# design1.net
KiCad netlist of a schematic drawn in EAGLE
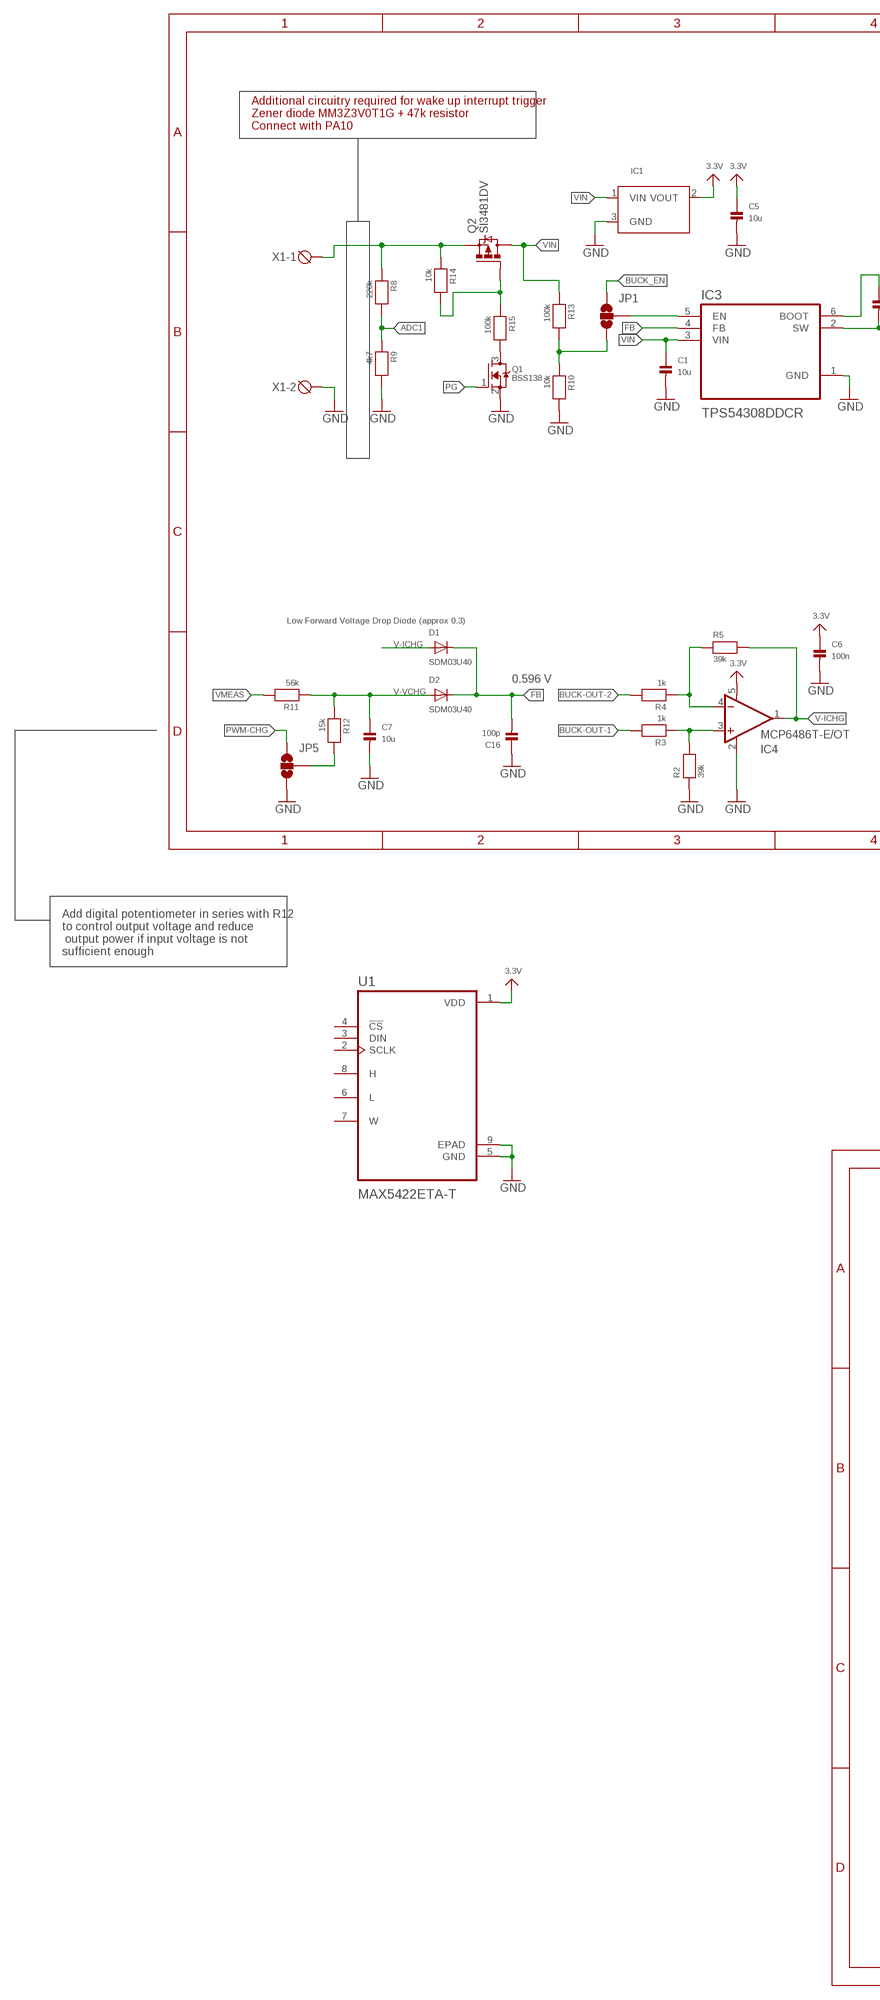
[diagram p0: schematic, sheet 1, part 1 of 2]
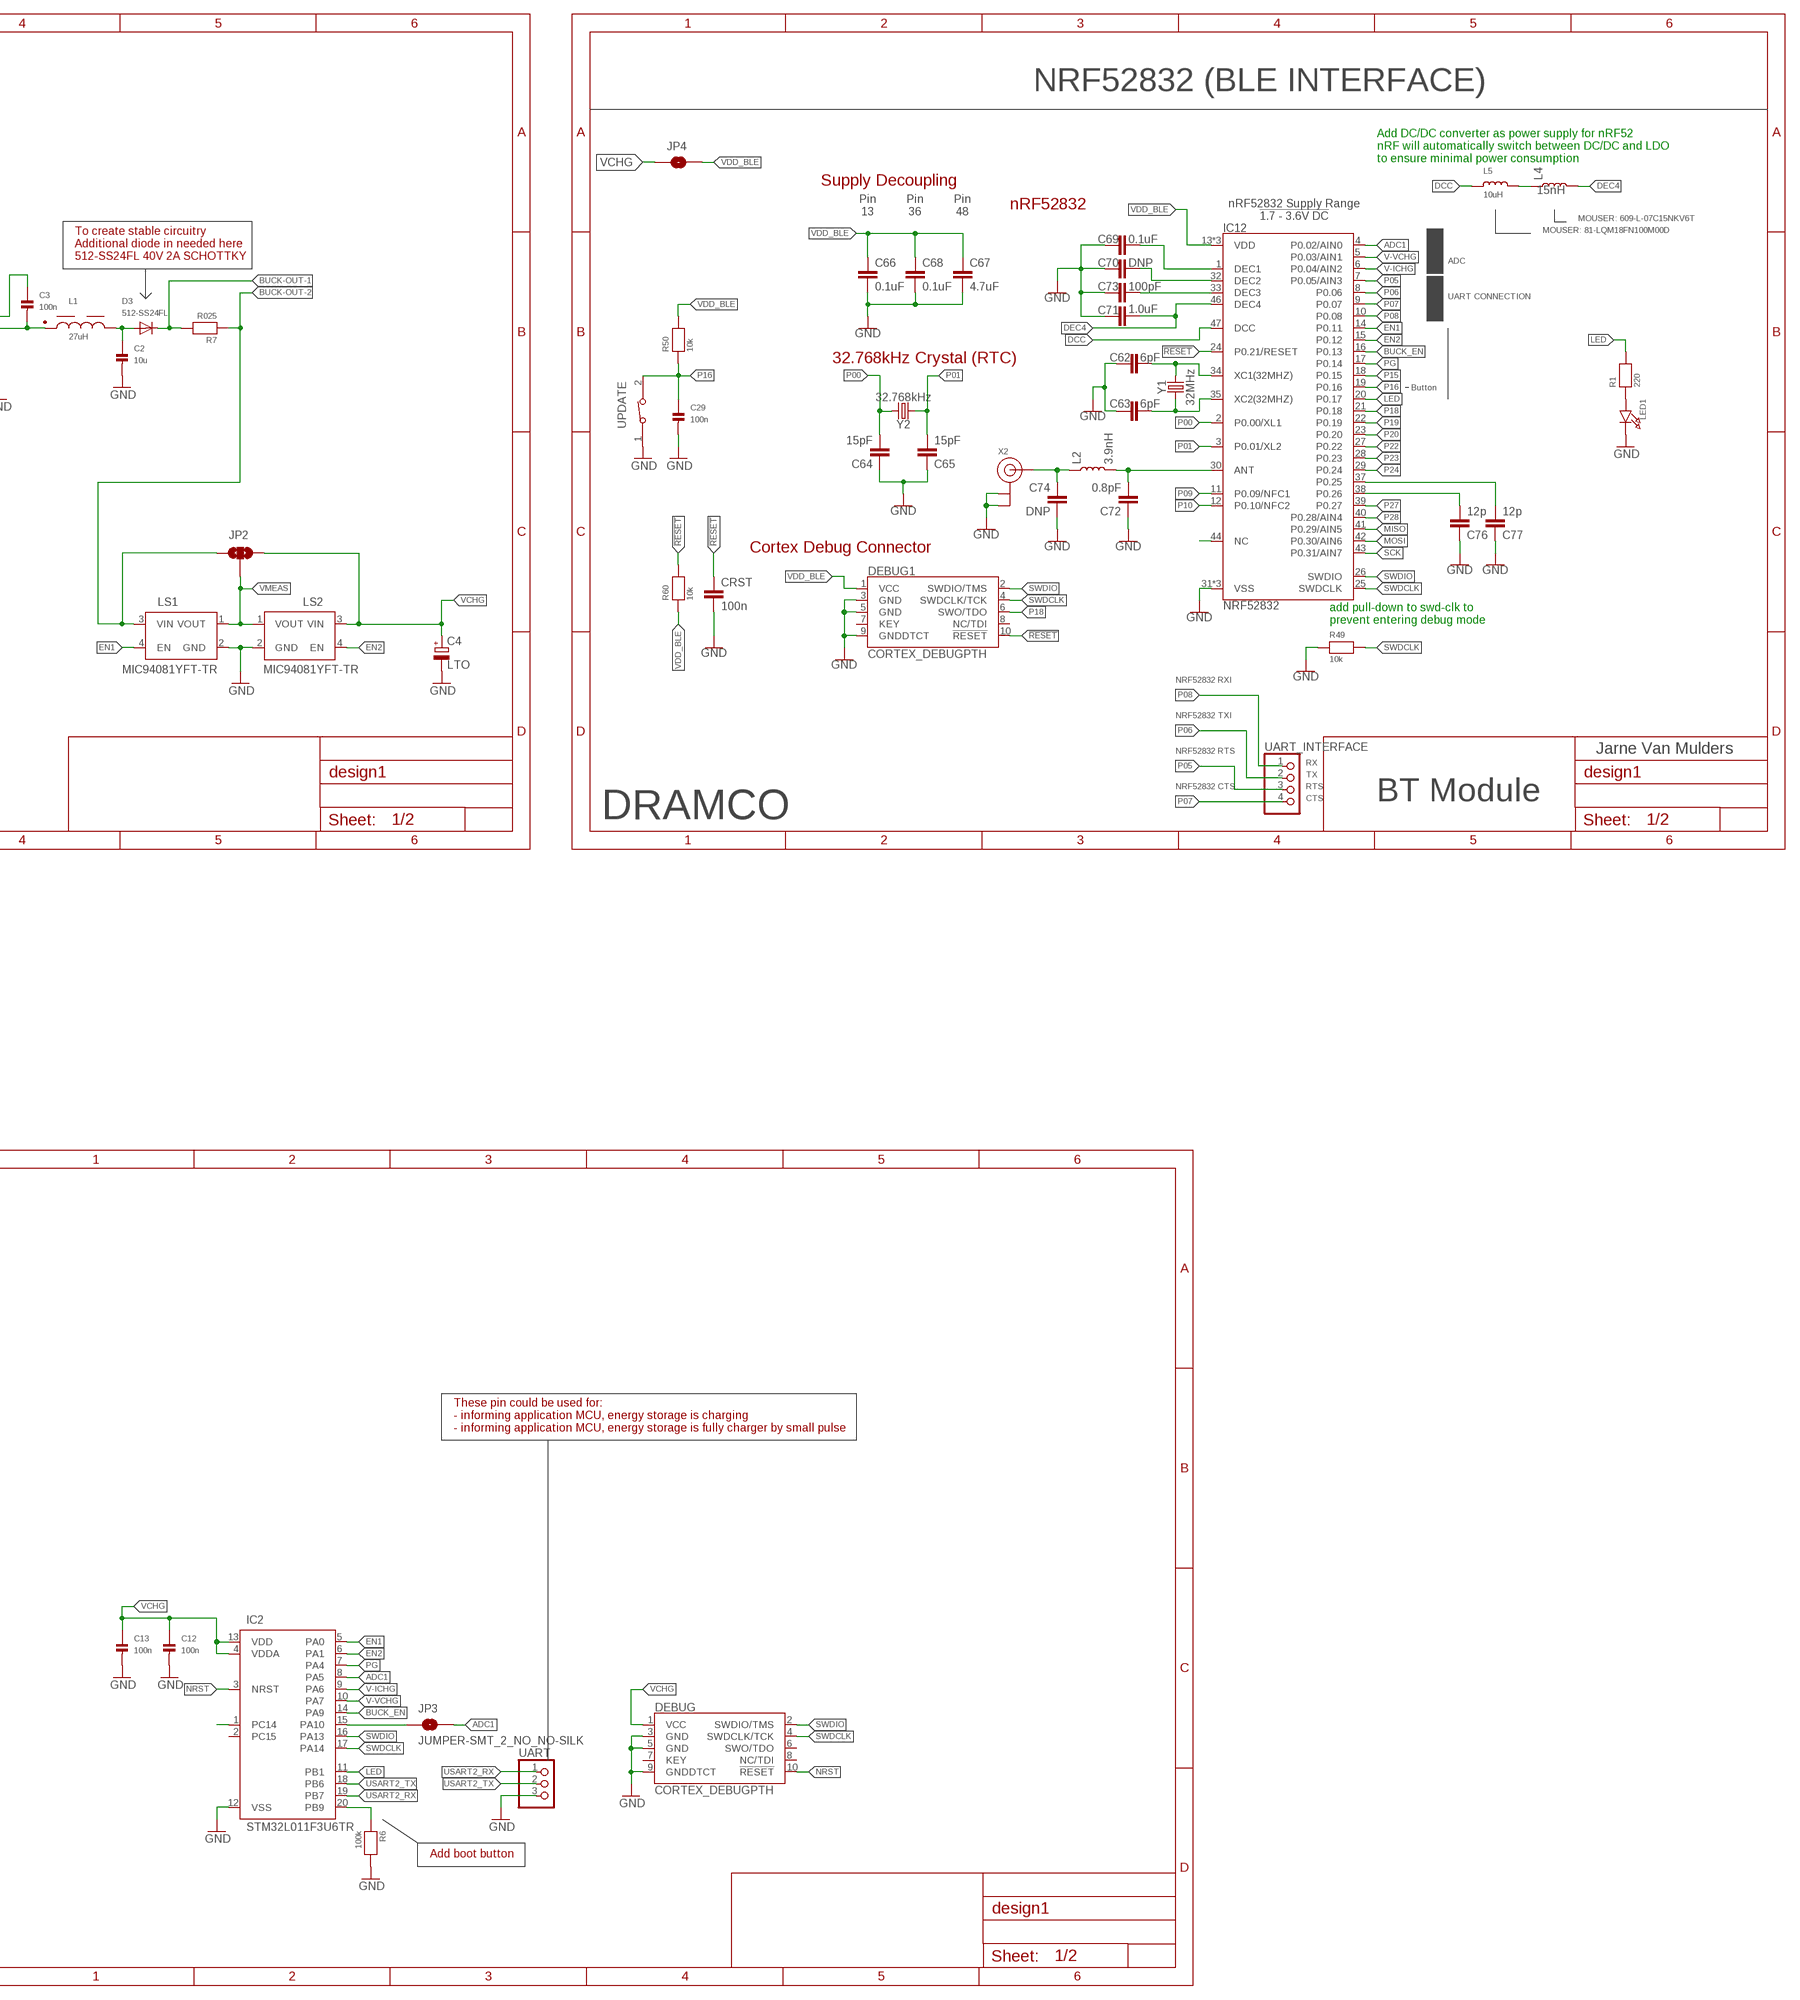
[diagram p1: schematic, sheet 1, part 2 of 2]

(export (version "E")
  (design (tool "Eeschema 10.0.6"))
  (components
    (comp (ref "C1")
      (value "10u")
      (footprint "eagle-import:0603")
      (libsource (lib "eagle-import") (part "CAP_CERAMIC0603"))
    )
    (comp (ref "C2")
      (value "10u")
      (footprint "eagle-import:0603")
      (libsource (lib "eagle-import") (part "CAP_CERAMIC0603"))
    )
    (comp (ref "C3")
      (value "100n")
      (footprint "eagle-import:0603")
      (libsource (lib "eagle-import") (part "CAP_CERAMIC0603"))
    )
    (comp (ref "C4")
      (value "LTO")
      (footprint "eagle-import:E5-10,5")
      (libsource (lib "eagle-import") (part "CPOL-EUE5-10.5"))
    )
    (comp (ref "C5")
      (value "10u")
      (footprint "eagle-import:0603")
      (libsource (lib "eagle-import") (part "CAP_CERAMIC0603"))
    )
    (comp (ref "C6")
      (value "100n")
      (footprint "eagle-import:0402")
      (libsource (lib "eagle-import") (part "CAP_CERAMIC0402"))
    )
    (comp (ref "C7")
      (value "10u")
      (footprint "eagle-import:0603")
      (libsource (lib "eagle-import") (part "CAP_CERAMIC0603"))
    )
    (comp (ref "C12")
      (value "100n")
      (footprint "eagle-import:0402")
      (libsource (lib "eagle-import") (part "CAP_CERAMIC0402"))
    )
    (comp (ref "C13")
      (value "100n")
      (footprint "eagle-import:0402")
      (libsource (lib "eagle-import") (part "CAP_CERAMIC0402"))
    )
    (comp (ref "C16")
      (value "100p")
      (footprint "eagle-import:0603")
      (libsource (lib "eagle-import") (part "CAP_CERAMIC0603"))
    )
    (comp (ref "C29")
      (value "100n")
      (footprint "eagle-import:0603")
      (libsource (lib "eagle-import") (part "CAP_CERAMIC0603"))
    )
    (comp (ref "C62")
      (value "6pF")
      (footprint "eagle-import:0402")
      (libsource (lib "eagle-import") (part "6PF-0402-50V-0.5%"))
    )
    (comp (ref "C63")
      (value "6pF")
      (footprint "eagle-import:0402")
      (libsource (lib "eagle-import") (part "6PF-0402-50V-0.5%"))
    )
    (comp (ref "C64")
      (value "15pF")
      (footprint "eagle-import:0402")
      (libsource (lib "eagle-import") (part "15PF-0402-50V-5%"))
    )
    (comp (ref "C65")
      (value "15pF")
      (footprint "eagle-import:0402")
      (libsource (lib "eagle-import") (part "15PF-0402-50V-5%"))
    )
    (comp (ref "C66")
      (value "0.1uF")
      (footprint "eagle-import:0402")
      (libsource (lib "eagle-import") (part "0.1UF-0402-16V-10%"))
    )
    (comp (ref "C67")
      (value "4.7uF")
      (footprint "eagle-import:0603")
      (libsource (lib "eagle-import") (part "4.7UF0603"))
    )
    (comp (ref "C68")
      (value "0.1uF")
      (footprint "eagle-import:0402")
      (libsource (lib "eagle-import") (part "0.1UF-0402-16V-10%"))
    )
    (comp (ref "C69")
      (value "0.1uF")
      (footprint "eagle-import:0402")
      (libsource (lib "eagle-import") (part "0.1UF-0402-16V-10%"))
    )
    (comp (ref "C70")
      (value "DNP")
      (footprint "eagle-import:0402")
      (libsource (lib "eagle-import") (part "CAP0402"))
    )
    (comp (ref "C71")
      (value "1.0uF")
      (footprint "eagle-import:0402")
      (libsource (lib "eagle-import") (part "1.0UF-0402-16V-10%"))
    )
    (comp (ref "C72")
      (value "0.8pF")
      (footprint "eagle-import:0402")
      (libsource (lib "eagle-import") (part "0.8PF-0402-50V-0.1PF"))
    )
    (comp (ref "C73")
      (value "100pF")
      (footprint "eagle-import:0402")
      (libsource (lib "eagle-import") (part "100PF-0402-50V-5%"))
    )
    (comp (ref "C74")
      (value "DNP")
      (footprint "eagle-import:0402")
      (libsource (lib "eagle-import") (part "CAP0402"))
    )
    (comp (ref "C76")
      (value "12p")
      (footprint "eagle-import:0402")
      (libsource (lib "eagle-import") (part "15PF-0402-50V-5%"))
    )
    (comp (ref "C77")
      (value "12p")
      (footprint "eagle-import:0402")
      (libsource (lib "eagle-import") (part "15PF-0402-50V-5%"))
    )
    (comp (ref "CRST")
      (value "100n")
      (footprint "eagle-import:C0603")
      (libsource (lib "eagle-import") (part "C-EUC0603"))
    )
    (comp (ref "D1")
      (value "SDM03U40")
      (footprint "eagle-import:SOD-523")
      (libsource (lib "eagle-import") (part "DIODESOD-523"))
    )
    (comp (ref "D2")
      (value "SDM03U40")
      (footprint "eagle-import:SOD-523")
      (libsource (lib "eagle-import") (part "DIODESOD-523"))
    )
    (comp (ref "D3")
      (value "512-SS24FL")
      (footprint "eagle-import:SOD-123")
      (libsource (lib "eagle-import") (part "DIODESOD-123"))
    )
    (comp (ref "DEBUG")
      (value "CORTEX_DEBUGPTH")
      (footprint "eagle-import:2X5-PTH-1.27MM")
      (libsource (lib "eagle-import") (part "CORTEX_DEBUGPTH"))
    )
    (comp (ref "DEBUG1")
      (value "CORTEX_DEBUGPTH")
      (footprint "eagle-import:2X5-PTH-1.27MM")
      (libsource (lib "eagle-import") (part "CORTEX_DEBUGPTH"))
    )
    (comp (ref "IC1")
      (value "VREG_SOT23")
      (footprint "eagle-import:SOT23-R")
      (libsource (lib "eagle-import") (part "VREG_SOT23"))
    )
    (comp (ref "IC2")
      (value "STM32L011F3U6TR")
      (footprint "eagle-import:QFN50P300X300X60-21N")
      (fields (field (name "MANUFACTURER") "STMicroelectronics"))
      (libsource (lib "eagle-import") (part "STM32L011F3U6TR"))
    )
    (comp (ref "IC3")
      (value "TPS54308DDCR")
      (footprint "eagle-import:SOT95P280X110-6N")
      (fields (field (name "MF") "Texas Instruments"))
      (libsource (lib "eagle-import") (part "TPS54308DDCR"))
    )
    (comp (ref "IC4")
      (value "MCP6486T-E/OT")
      (footprint "eagle-import:SOT23-5")
      (libsource (lib "eagle-import") (part "MCP6291T-E/OT"))
    )
    (comp (ref "IC12")
      (value "NRF52832")
      (footprint "eagle-import:QFN48-6X6MM")
      (libsource (lib "eagle-import") (part "NRF52832"))
    )
    (comp (ref "JP1")
      (value "JUMPER-SMT_3_NO_NO-SILK")
      (footprint "eagle-import:SMT-JUMPER_3_NO_NO-SILK")
      (libsource (lib "eagle-import") (part "JUMPER-SMT_3_NO_NO-SILK"))
    )
    (comp (ref "JP2")
      (value "JUMPER-SMT_3_NO_NO-SILK")
      (footprint "eagle-import:SMT-JUMPER_3_NO_NO-SILK")
      (libsource (lib "eagle-import") (part "JUMPER-SMT_3_NO_NO-SILK"))
    )
    (comp (ref "JP3")
      (value "JUMPER-SMT_2_NO_NO-SILK")
      (footprint "eagle-import:SMT-JUMPER_2_NO_NO-SILK")
      (libsource (lib "eagle-import") (part "JUMPER-SMT_2_NO_NO-SILK"))
    )
    (comp (ref "JP4")
      (value "JUMPER-SMT_2_NO_NO-SILK")
      (footprint "eagle-import:SMT-JUMPER_2_NO_NO-SILK")
      (libsource (lib "eagle-import") (part "JUMPER-SMT_2_NO_NO-SILK"))
    )
    (comp (ref "JP5")
      (value "JUMPER-SMT_3_NO_NO-SILK")
      (footprint "eagle-import:SMT-JUMPER_3_NO_NO-SILK")
      (libsource (lib "eagle-import") (part "JUMPER-SMT_3_NO_NO-SILK"))
    )
    (comp (ref "L1")
      (value "27uH")
      (footprint "eagle-import:WE-PD_7332_7345_PLASTIC_BASE")
      (libsource (lib "eagle-import") (part "WE-PD_7332_PLASTIC_7447789127"))
    )
    (comp (ref "L2")
      (value "3.9nH")
      (footprint "eagle-import:0402")
      (libsource (lib "eagle-import") (part "INDUCTOR-0402-3.9NH"))
    )
    (comp (ref "L4")
      (value "15nH")
      (footprint "eagle-import:0402")
      (libsource (lib "eagle-import") (part "INDUCTOR-0402-3.9NH"))
    )
    (comp (ref "L5")
      (value "10uH")
      (footprint "eagle-import:_0603MP")
      (libsource (lib "eagle-import") (part "INDUCTOR_0603MP"))
    )
    (comp (ref "LED1")
      (value "LED0805")
      (footprint "eagle-import:CHIPLED_0805")
      (libsource (lib "eagle-import") (part "LED0805"))
    )
    (comp (ref "LS1")
      (value "MIC94081YFT-TR")
      (footprint "eagle-import:IC_MIC94081YFT-TR")
      (fields (field (name "MF") "Microchip"))
      (libsource (lib "eagle-import") (part "MIC94081YFT-TR"))
    )
    (comp (ref "LS2")
      (value "MIC94081YFT-TR")
      (footprint "eagle-import:IC_MIC94081YFT-TR")
      (fields (field (name "MF") "Microchip"))
      (libsource (lib "eagle-import") (part "MIC94081YFT-TR"))
    )
    (comp (ref "Q1")
      (value "BSS138")
      (footprint "eagle-import:SOT23-R")
      (libsource (lib "eagle-import") (part "MOSFET-NREFLOW"))
    )
    (comp (ref "Q2")
      (value "SI3481DV")
      (footprint "eagle-import:TSOP-6.PAC")
      (libsource (lib "eagle-import") (part "SI3481DV"))
    )
    (comp (ref "R1")
      (value "220")
      (footprint "eagle-import:0603")
      (libsource (lib "eagle-import") (part "RESISTOR0603"))
    )
    (comp (ref "R2")
      (value "39k")
      (footprint "eagle-import:0603")
      (libsource (lib "eagle-import") (part "RESISTOR0603"))
    )
    (comp (ref "R3")
      (value "1k")
      (footprint "eagle-import:0603")
      (libsource (lib "eagle-import") (part "RESISTOR0603"))
    )
    (comp (ref "R4")
      (value "1k")
      (footprint "eagle-import:0603")
      (libsource (lib "eagle-import") (part "RESISTOR0603"))
    )
    (comp (ref "R5")
      (value "39k")
      (footprint "eagle-import:0603")
      (libsource (lib "eagle-import") (part "RESISTOR0603"))
    )
    (comp (ref "R6")
      (value "100k")
      (footprint "eagle-import:0603")
      (libsource (lib "eagle-import") (part "RESISTOR0603"))
    )
    (comp (ref "R7")
      (value "R025")
      (footprint "eagle-import:0603")
      (libsource (lib "eagle-import") (part "RESISTOR0603"))
    )
    (comp (ref "R8")
      (value "220k")
      (footprint "eagle-import:0603")
      (libsource (lib "eagle-import") (part "RESISTOR0603"))
    )
    (comp (ref "R9")
      (value "4k7")
      (footprint "eagle-import:0603")
      (libsource (lib "eagle-import") (part "RESISTOR0603"))
    )
    (comp (ref "R10")
      (value "10k")
      (footprint "eagle-import:0603")
      (libsource (lib "eagle-import") (part "RESISTOR0603"))
    )
    (comp (ref "R11")
      (value "56k")
      (footprint "eagle-import:0603")
      (libsource (lib "eagle-import") (part "RESISTOR0603"))
    )
    (comp (ref "R12")
      (value "15k")
      (footprint "eagle-import:0603")
      (libsource (lib "eagle-import") (part "RESISTOR0603"))
    )
    (comp (ref "R13")
      (value "100k")
      (footprint "eagle-import:0603")
      (libsource (lib "eagle-import") (part "RESISTOR0603"))
    )
    (comp (ref "R14")
      (value "10k")
      (footprint "eagle-import:0603")
      (libsource (lib "eagle-import") (part "RESISTOR0603"))
    )
    (comp (ref "R15")
      (value "100k")
      (footprint "eagle-import:0603")
      (libsource (lib "eagle-import") (part "RESISTOR0603"))
    )
    (comp (ref "R49")
      (value "10k")
      (footprint "eagle-import:0603")
      (libsource (lib "eagle-import") (part "RESISTOR0603"))
    )
    (comp (ref "R50")
      (value "10k")
      (footprint "eagle-import:0603")
      (libsource (lib "eagle-import") (part "RESISTOR0603"))
    )
    (comp (ref "R60")
      (value "10k")
      (footprint "eagle-import:0603")
      (libsource (lib "eagle-import") (part "RESISTOR0603"))
    )
    (comp (ref "U1")
      (value "MAX5422ETA-T")
      (footprint "eagle-import:SON65P300X300X80-9N")
      (fields (field (name "MF") "Analog Devices") (field (name "MP") "MAX5422ETA"))
      (libsource (lib "eagle-import") (part "MAX5422ETA-T"))
    )
    (comp (ref "UART")
      (value "HEADER-1X3ROUND")
      (footprint "eagle-import:1X03_ROUND")
      (libsource (lib "eagle-import") (part "HEADER-1X3ROUND"))
    )
    (comp (ref "UART_INTERFACE")
      (value "HEADER-1X4ROUND")
      (footprint "eagle-import:1X04_ROUND")
      (libsource (lib "eagle-import") (part "HEADER-1X4ROUND"))
    )
    (comp (ref "UPDATE")
      (value "434111043826")
      (footprint "eagle-import:434111043826")
      (libsource (lib "eagle-import") (part "434111043826"))
    )
    (comp (ref "X1")
      (value "DG3XX-02-5.0")
      (footprint "eagle-import:DG306-5.0-02P")
      (libsource (lib "eagle-import") (part "DG3XX-02-5.0"))
    )
    (comp (ref "X2")
      (value "ANTENNA_U.FL")
      (footprint "eagle-import:U.FL")
      (libsource (lib "eagle-import") (part "ANTENNA_U.FL"))
    )
    (comp (ref "Y1")
      (value "32MHz")
      (footprint "eagle-import:CRYSTAL-SMD-2.0X1.6MM")
      (libsource (lib "eagle-import") (part "CRYSTAL-32MHZ-SMD-2.0X1.6MM"))
    )
    (comp (ref "Y2")
      (value "32.768kHz")
      (footprint "eagle-import:CRYSTAL-SMD-3.2X1.5MM")
      (libsource (lib "eagle-import") (part "CRYSTAL-32.768KHZSMD-3.2X1.5"))
    )
  )
  (nets
    (net (code "1") (name "3.3V") (class "Default")
      (node (ref "C5") (pin "1") (pinfunction "P$1_1") (pintype "passive"))
      (node (ref "C6") (pin "1") (pinfunction "P$1_1") (pintype "passive"))
      (node (ref "IC1") (pin "2") (pinfunction "VOUT_2") (pintype "power_in"))
      (node (ref "IC4") (pin "5") (pinfunction "V+_5") (pintype "power_in"))
      (node (ref "U1") (pin "1") (pinfunction "VDD_1") (pintype "power_in"))
    )
    (net (code "2") (name "ADC1") (class "Default")
      (node (ref "IC12") (pin "4") (pinfunction "P0.02/AIN0_4") (pintype "bidirectional"))
      (node (ref "IC2") (pin "8") (pinfunction "PA5_8") (pintype "bidirectional"))
      (node (ref "JP3") (pin "2") (pinfunction "2_2") (pintype "passive"))
      (node (ref "R8") (pin "2") (pinfunction "2_2") (pintype "passive"))
      (node (ref "R9") (pin "1") (pinfunction "1_1") (pintype "passive"))
    )
    (net (code "3") (name "BUCK-OUT-1") (class "Default")
      (node (ref "D3") (pin "C") (pinfunction "C_C") (pintype "passive"))
      (node (ref "R3") (pin "2") (pinfunction "2_2") (pintype "passive"))
      (node (ref "R7") (pin "2") (pinfunction "2_2") (pintype "passive"))
    )
    (net (code "4") (name "BUCK-OUT-2") (class "Default")
      (node (ref "JP2") (pin "1") (pinfunction "1_1") (pintype "passive"))
      (node (ref "LS1") (pin "3") (pinfunction "VIN_3") (pintype "input"))
      (node (ref "R4") (pin "2") (pinfunction "2_2") (pintype "passive"))
      (node (ref "R7") (pin "1") (pinfunction "1_1") (pintype "passive"))
    )
    (net (code "5") (name "BUCK_EN") (class "Default")
      (node (ref "IC12") (pin "16") (pinfunction "P0.13_16") (pintype "bidirectional"))
      (node (ref "IC2") (pin "14") (pinfunction "PA9_14") (pintype "bidirectional"))
      (node (ref "JP1") (pin "3") (pinfunction "3_3") (pintype "passive"))
    )
    (net (code "6") (name "DCC") (class "Default")
      (node (ref "IC12") (pin "47") (pinfunction "DCC_47") (pintype "bidirectional"))
      (node (ref "L5") (pin "1") (pinfunction "1_1") (pintype "passive"))
    )
    (net (code "7") (name "DEC4") (class "Default")
      (node (ref "C71") (pin "2") (pinfunction "2_2") (pintype "passive"))
      (node (ref "IC12") (pin "46") (pinfunction "DEC4_46") (pintype "bidirectional"))
      (node (ref "L4") (pin "2") (pinfunction "2_2") (pintype "passive"))
    )
    (net (code "8") (name "EN1") (class "Default")
      (node (ref "IC12") (pin "14") (pinfunction "P0.11_14") (pintype "bidirectional"))
      (node (ref "IC2") (pin "5") (pinfunction "PA0_5") (pintype "bidirectional"))
      (node (ref "LS1") (pin "4") (pinfunction "EN_4") (pintype "input"))
    )
    (net (code "9") (name "EN2") (class "Default")
      (node (ref "IC12") (pin "15") (pinfunction "P0.12_15") (pintype "bidirectional"))
      (node (ref "IC2") (pin "6") (pinfunction "PA1_6") (pintype "bidirectional"))
      (node (ref "LS2") (pin "4") (pinfunction "EN_4") (pintype "input"))
    )
    (net (code "10") (name "FB") (class "Default")
      (node (ref "C16") (pin "2") (pinfunction "P$2_2") (pintype "passive"))
      (node (ref "D1") (pin "K") (pinfunction "C_K") (pintype "passive"))
      (node (ref "D2") (pin "K") (pinfunction "C_K") (pintype "passive"))
      (node (ref "IC3") (pin "4") (pinfunction "FB_4") (pintype "input"))
    )
    (net (code "11") (name "GND") (class "Default")
      (node (ref "C1") (pin "2") (pinfunction "P$2_2") (pintype "passive"))
      (node (ref "C12") (pin "2") (pinfunction "P$2_2") (pintype "passive"))
      (node (ref "C13") (pin "2") (pinfunction "P$2_2") (pintype "passive"))
      (node (ref "C16") (pin "1") (pinfunction "P$1_1") (pintype "passive"))
      (node (ref "C2") (pin "2") (pinfunction "P$2_2") (pintype "passive"))
      (node (ref "C29") (pin "2") (pinfunction "P$2_2") (pintype "passive"))
      (node (ref "C4") (pin "-") (pinfunction "-_-") (pintype "passive"))
      (node (ref "C5") (pin "2") (pinfunction "P$2_2") (pintype "passive"))
      (node (ref "C6") (pin "2") (pinfunction "P$2_2") (pintype "passive"))
      (node (ref "C62") (pin "1") (pinfunction "1_1") (pintype "passive"))
      (node (ref "C63") (pin "2") (pinfunction "2_2") (pintype "passive"))
      (node (ref "C64") (pin "1") (pinfunction "1_1") (pintype "passive"))
      (node (ref "C65") (pin "1") (pinfunction "1_1") (pintype "passive"))
      (node (ref "C66") (pin "2") (pinfunction "2_2") (pintype "passive"))
      (node (ref "C67") (pin "2") (pinfunction "2_2") (pintype "passive"))
      (node (ref "C68") (pin "2") (pinfunction "2_2") (pintype "passive"))
      (node (ref "C69") (pin "1") (pinfunction "1_1") (pintype "passive"))
      (node (ref "C7") (pin "2") (pinfunction "P$2_2") (pintype "passive"))
      (node (ref "C70") (pin "1") (pinfunction "1_1") (pintype "passive"))
      (node (ref "C71") (pin "1") (pinfunction "1_1") (pintype "passive"))
      (node (ref "C72") (pin "1") (pinfunction "1_1") (pintype "passive"))
      (node (ref "C73") (pin "1") (pinfunction "1_1") (pintype "passive"))
      (node (ref "C74") (pin "2") (pinfunction "2_2") (pintype "passive"))
      (node (ref "C76") (pin "1") (pinfunction "1_1") (pintype "passive"))
      (node (ref "C77") (pin "1") (pinfunction "1_1") (pintype "passive"))
      (node (ref "CRST") (pin "2") (pinfunction "2_2") (pintype "passive"))
      (node (ref "DEBUG") (pin "3") (pinfunction "GND_3") (pintype "bidirectional"))
      (node (ref "DEBUG") (pin "5") (pinfunction "GND_5") (pintype "bidirectional"))
      (node (ref "DEBUG") (pin "9") (pinfunction "GNDDTCT_9") (pintype "bidirectional"))
      (node (ref "DEBUG1") (pin "3") (pinfunction "GND_3") (pintype "bidirectional"))
      (node (ref "DEBUG1") (pin "5") (pinfunction "GND_5") (pintype "bidirectional"))
      (node (ref "DEBUG1") (pin "9") (pinfunction "GNDDTCT_9") (pintype "bidirectional"))
      (node (ref "IC1") (pin "3") (pinfunction "GND_3") (pintype "power_in"))
      (node (ref "IC12") (pin "31") (pinfunction "VSS_31") (pintype "bidirectional"))
      (node (ref "IC12") (pin "45") (pinfunction "VSS_45") (pintype "bidirectional"))
      (node (ref "IC12") (pin "EP") (pinfunction "VSS_EP") (pintype "bidirectional"))
      (node (ref "IC2") (pin "12") (pinfunction "VSS_12") (pintype "bidirectional"))
      (node (ref "IC3") (pin "1") (pinfunction "GND_1") (pintype "power_in"))
      (node (ref "IC4") (pin "2") (pinfunction "V-_2") (pintype "power_in"))
      (node (ref "JP5") (pin "1") (pinfunction "1_1") (pintype "passive"))
      (node (ref "LED1") (pin "C") (pinfunction "C_C") (pintype "passive"))
      (node (ref "LS1") (pin "2") (pinfunction "GND_2") (pintype "power_in"))
      (node (ref "LS2") (pin "2") (pinfunction "GND_2") (pintype "power_in"))
      (node (ref "Q1") (pin "2") (pinfunction "S_2") (pintype "bidirectional"))
      (node (ref "R10") (pin "2") (pinfunction "2_2") (pintype "passive"))
      (node (ref "R2") (pin "1") (pinfunction "1_1") (pintype "passive"))
      (node (ref "R49") (pin "1") (pinfunction "1_1") (pintype "passive"))
      (node (ref "R6") (pin "2") (pinfunction "2_2") (pintype "passive"))
      (node (ref "R9") (pin "2") (pinfunction "2_2") (pintype "passive"))
      (node (ref "U1") (pin "5") (pinfunction "GND_5") (pintype "power_in"))
      (node (ref "U1") (pin "9") (pinfunction "EPAD_9") (pintype "power_in"))
      (node (ref "UART") (pin "3") (pinfunction "3_3") (pintype "passive"))
      (node (ref "UPDATE") (pin "1") (pinfunction "1_1") (pintype "passive"))
      (node (ref "X1") (pin "2") (pinfunction "KL_2") (pintype "passive"))
      (node (ref "X2") (pin "1") (pinfunction "GND_1") (pintype "passive"))
      (node (ref "X2") (pin "2") (pinfunction "GND_2") (pintype "passive"))
    )
    (net (code "12") (name "LED") (class "Default")
      (node (ref "IC12") (pin "20") (pinfunction "P0.17_20") (pintype "bidirectional"))
      (node (ref "IC2") (pin "11") (pinfunction "PB1_11") (pintype "bidirectional"))
      (node (ref "R1") (pin "2") (pinfunction "2_2") (pintype "passive"))
    )
    (net (code "13") (name "MISO") (class "Default")
      (node (ref "IC12") (pin "41") (pinfunction "P0.29/AIN5_41") (pintype "bidirectional"))
    )
    (net (code "14") (name "MOSI") (class "Default")
      (node (ref "IC12") (pin "42") (pinfunction "P0.30/AIN6_42") (pintype "bidirectional"))
    )
    (net (code "15") (name "NRST") (class "Default")
      (node (ref "DEBUG") (pin "10") (pinfunction "~{RESET}_10") (pintype "bidirectional"))
      (node (ref "IC2") (pin "3") (pinfunction "NRST_3") (pintype "bidirectional"))
    )
    (net (code "16") (name "Net-(C2-P$1)") (class "Default")
      (node (ref "C2") (pin "1") (pinfunction "P$1_1") (pintype "passive"))
      (node (ref "D3") (pin "A") (pinfunction "A_A") (pintype "passive"))
      (node (ref "L1") (pin "2") (pinfunction "2_2") (pintype "passive"))
    )
    (net (code "17") (name "Net-(C3-P$1)") (class "Default")
      (node (ref "C3") (pin "1") (pinfunction "P$1_1") (pintype "passive"))
      (node (ref "IC3") (pin "6") (pinfunction "BOOT_6") (pintype "output"))
    )
    (net (code "18") (name "Net-(C3-P$2)") (class "Default")
      (node (ref "C3") (pin "2") (pinfunction "P$2_2") (pintype "passive"))
      (node (ref "IC3") (pin "2") (pinfunction "SW_2") (pintype "output"))
      (node (ref "L1") (pin "1") (pinfunction "1_1") (pintype "passive"))
    )
    (net (code "19") (name "Net-(IC2-PA10)") (class "Default")
      (node (ref "IC2") (pin "15") (pinfunction "PA10_15") (pintype "bidirectional"))
      (node (ref "JP3") (pin "1") (pinfunction "1_1") (pintype "passive"))
    )
    (net (code "20") (name "Net-(IC2-PB9)") (class "Default")
      (node (ref "IC2") (pin "20") (pinfunction "PB9_20") (pintype "bidirectional"))
      (node (ref "R6") (pin "1") (pinfunction "1_1") (pintype "passive"))
    )
    (net (code "21") (name "Net-(IC3-EN)") (class "Default")
      (node (ref "IC3") (pin "5") (pinfunction "EN_5") (pintype "input"))
      (node (ref "JP1") (pin "2") (pinfunction "2_2") (pintype "passive"))
    )
    (net (code "22") (name "Net-(IC4-+IN)") (class "Default")
      (node (ref "IC4") (pin "3") (pinfunction "+IN_3") (pintype "input"))
      (node (ref "R2") (pin "2") (pinfunction "2_2") (pintype "passive"))
      (node (ref "R3") (pin "1") (pinfunction "1_1") (pintype "passive"))
    )
    (net (code "23") (name "Net-(IC4--IN)") (class "Default")
      (node (ref "IC4") (pin "4") (pinfunction "-IN_4") (pintype "input"))
      (node (ref "R4") (pin "1") (pinfunction "1_1") (pintype "passive"))
      (node (ref "R5") (pin "1") (pinfunction "1_1") (pintype "passive"))
    )
    (net (code "24") (name "Net-(IC12-ANT)") (class "Default")
      (node (ref "C72") (pin "2") (pinfunction "2_2") (pintype "passive"))
      (node (ref "IC12") (pin "30") (pinfunction "ANT_30") (pintype "bidirectional"))
      (node (ref "L2") (pin "2") (pinfunction "2_2") (pintype "passive"))
    )
    (net (code "25") (name "Net-(IC12-DEC1)") (class "Default")
      (node (ref "C69") (pin "2") (pinfunction "2_2") (pintype "passive"))
      (node (ref "IC12") (pin "1") (pinfunction "DEC1_1") (pintype "bidirectional"))
    )
    (net (code "26") (name "Net-(IC12-DEC2)") (class "Default")
      (node (ref "C70") (pin "2") (pinfunction "2_2") (pintype "passive"))
      (node (ref "IC12") (pin "32") (pinfunction "DEC2_32") (pintype "bidirectional"))
    )
    (net (code "27") (name "Net-(IC12-DEC3)") (class "Default")
      (node (ref "C73") (pin "2") (pinfunction "2_2") (pintype "passive"))
      (node (ref "IC12") (pin "33") (pinfunction "DEC3_33") (pintype "bidirectional"))
    )
    (net (code "28") (name "Net-(IC12-P0.25)") (class "Default")
      (node (ref "C77") (pin "2") (pinfunction "2_2") (pintype "passive"))
      (node (ref "IC12") (pin "37") (pinfunction "P0.25_37") (pintype "bidirectional"))
    )
    (net (code "29") (name "Net-(IC12-P0.26)") (class "Default")
      (node (ref "C76") (pin "2") (pinfunction "2_2") (pintype "passive"))
      (node (ref "IC12") (pin "38") (pinfunction "P0.26_38") (pintype "bidirectional"))
    )
    (net (code "30") (name "Net-(IC12-XC1(32MHZ))") (class "Default")
      (node (ref "C62") (pin "2") (pinfunction "2_2") (pintype "passive"))
      (node (ref "IC12") (pin "34") (pinfunction "XC1(32MHZ)_34") (pintype "bidirectional"))
      (node (ref "Y1") (pin "3") (pinfunction "2_3") (pintype "passive"))
    )
    (net (code "31") (name "Net-(IC12-XC2(32MHZ))") (class "Default")
      (node (ref "C63") (pin "1") (pinfunction "1_1") (pintype "passive"))
      (node (ref "IC12") (pin "35") (pinfunction "XC2(32MHZ)_35") (pintype "bidirectional"))
      (node (ref "Y1") (pin "1") (pinfunction "1_1") (pintype "passive"))
    )
    (net (code "32") (name "Net-(JP1-Pad1)") (class "Default")
      (node (ref "JP1") (pin "1") (pinfunction "1_1") (pintype "passive"))
      (node (ref "R10") (pin "1") (pinfunction "1_1") (pintype "passive"))
      (node (ref "R13") (pin "2") (pinfunction "2_2") (pintype "passive"))
    )
    (net (code "33") (name "Net-(JP5-Pad2)") (class "Default")
      (node (ref "JP5") (pin "2") (pinfunction "2_2") (pintype "passive"))
      (node (ref "R12") (pin "2") (pinfunction "2_2") (pintype "passive"))
    )
    (net (code "34") (name "Net-(L4-Pad1)") (class "Default")
      (node (ref "L4") (pin "1") (pinfunction "1_1") (pintype "passive"))
      (node (ref "L5") (pin "2") (pinfunction "2_2") (pintype "passive"))
    )
    (net (code "35") (name "Net-(LED1-PadA)") (class "Default")
      (node (ref "LED1") (pin "A") (pinfunction "A_A") (pintype "passive"))
      (node (ref "R1") (pin "1") (pinfunction "1_1") (pintype "passive"))
    )
    (net (code "36") (name "Net-(Q1-D)") (class "Default")
      (node (ref "Q1") (pin "3") (pinfunction "D_3") (pintype "bidirectional"))
      (node (ref "R15") (pin "2") (pinfunction "2_2") (pintype "passive"))
    )
    (net (code "37") (name "Net-(Q2-G)") (class "Default")
      (node (ref "Q2") (pin "3") (pinfunction "G_3") (pintype "passive"))
      (node (ref "R14") (pin "2") (pinfunction "2_2") (pintype "passive"))
      (node (ref "R15") (pin "1") (pinfunction "1_1") (pintype "passive"))
    )
    (net (code "38") (name "Net-(Q2-S)") (class "Default")
      (node (ref "Q2") (pin "4") (pinfunction "S_4") (pintype "passive"))
      (node (ref "R14") (pin "1") (pinfunction "1_1") (pintype "passive"))
      (node (ref "R8") (pin "1") (pinfunction "1_1") (pintype "passive"))
      (node (ref "X1") (pin "1") (pinfunction "KL_1") (pintype "passive"))
    )
    (net (code "39") (name "Net-(X2-SIGNAL)") (class "Default")
      (node (ref "C74") (pin "1") (pinfunction "1_1") (pintype "passive"))
      (node (ref "L2") (pin "1") (pinfunction "1_1") (pintype "passive"))
      (node (ref "X2") (pin "3") (pinfunction "SIGNAL_3") (pintype "passive"))
    )
    (net (code "40") (name "P00") (class "Default")
      (node (ref "C64") (pin "2") (pinfunction "2_2") (pintype "passive"))
      (node (ref "IC12") (pin "2") (pinfunction "P0.00/XL1_2") (pintype "bidirectional"))
      (node (ref "Y2") (pin "P$2") (pinfunction "2_P$2") (pintype "passive"))
    )
    (net (code "41") (name "P01") (class "Default")
      (node (ref "C65") (pin "2") (pinfunction "2_2") (pintype "passive"))
      (node (ref "IC12") (pin "3") (pinfunction "P0.01/XL2_3") (pintype "bidirectional"))
      (node (ref "Y2") (pin "P$1") (pinfunction "1_P$1") (pintype "passive"))
    )
    (net (code "42") (name "P05") (class "Default")
      (node (ref "IC12") (pin "7") (pinfunction "P0.05/AIN3_7") (pintype "bidirectional"))
      (node (ref "UART_INTERFACE") (pin "3") (pinfunction "3_3") (pintype "passive"))
    )
    (net (code "43") (name "P06") (class "Default")
      (node (ref "IC12") (pin "8") (pinfunction "P0.06_8") (pintype "bidirectional"))
      (node (ref "UART_INTERFACE") (pin "2") (pinfunction "2_2") (pintype "passive"))
    )
    (net (code "44") (name "P07") (class "Default")
      (node (ref "IC12") (pin "9") (pinfunction "P0.07_9") (pintype "bidirectional"))
      (node (ref "UART_INTERFACE") (pin "4") (pinfunction "4_4") (pintype "passive"))
    )
    (net (code "45") (name "P08") (class "Default")
      (node (ref "IC12") (pin "10") (pinfunction "P0.08_10") (pintype "bidirectional"))
      (node (ref "UART_INTERFACE") (pin "1") (pinfunction "1_1") (pintype "passive"))
    )
    (net (code "46") (name "P09") (class "Default")
      (node (ref "IC12") (pin "11") (pinfunction "P0.09/NFC1_11") (pintype "bidirectional"))
    )
    (net (code "47") (name "P10") (class "Default")
      (node (ref "IC12") (pin "12") (pinfunction "P0.10/NFC2_12") (pintype "bidirectional"))
    )
    (net (code "48") (name "P15") (class "Default")
      (node (ref "IC12") (pin "18") (pinfunction "P0.15_18") (pintype "bidirectional"))
    )
    (net (code "49") (name "P16") (class "Default")
      (node (ref "C29") (pin "1") (pinfunction "P$1_1") (pintype "passive"))
      (node (ref "IC12") (pin "19") (pinfunction "P0.16_19") (pintype "bidirectional"))
      (node (ref "R50") (pin "1") (pinfunction "1_1") (pintype "passive"))
      (node (ref "UPDATE") (pin "2") (pinfunction "2_2") (pintype "passive"))
    )
    (net (code "50") (name "P18") (class "Default")
      (node (ref "DEBUG1") (pin "6") (pinfunction "SWO/TDO_6") (pintype "bidirectional"))
      (node (ref "IC12") (pin "21") (pinfunction "P0.18_21") (pintype "bidirectional"))
    )
    (net (code "51") (name "P19") (class "Default")
      (node (ref "IC12") (pin "22") (pinfunction "P0.19_22") (pintype "bidirectional"))
    )
    (net (code "52") (name "P20") (class "Default")
      (node (ref "IC12") (pin "23") (pinfunction "P0.20_23") (pintype "bidirectional"))
    )
    (net (code "53") (name "P22") (class "Default")
      (node (ref "IC12") (pin "27") (pinfunction "P0.22_27") (pintype "bidirectional"))
    )
    (net (code "54") (name "P23") (class "Default")
      (node (ref "IC12") (pin "28") (pinfunction "P0.23_28") (pintype "bidirectional"))
    )
    (net (code "55") (name "P24") (class "Default")
      (node (ref "IC12") (pin "29") (pinfunction "P0.24_29") (pintype "bidirectional"))
    )
    (net (code "56") (name "P27") (class "Default")
      (node (ref "IC12") (pin "39") (pinfunction "P0.27_39") (pintype "bidirectional"))
    )
    (net (code "57") (name "P28") (class "Default")
      (node (ref "IC12") (pin "40") (pinfunction "P0.28/AIN4_40") (pintype "bidirectional"))
    )
    (net (code "58") (name "PG") (class "Default")
      (node (ref "IC12") (pin "17") (pinfunction "P0.14_17") (pintype "bidirectional"))
      (node (ref "IC2") (pin "7") (pinfunction "PA4_7") (pintype "bidirectional"))
      (node (ref "Q1") (pin "1") (pinfunction "G_1") (pintype "bidirectional"))
    )
    (net (code "59") (name "PWM-CHG") (class "Default")
      (node (ref "JP5") (pin "3") (pinfunction "3_3") (pintype "passive"))
    )
    (net (code "60") (name "SCK") (class "Default")
      (node (ref "IC12") (pin "43") (pinfunction "P0.31/AIN7_43") (pintype "bidirectional"))
    )
    (net (code "61") (name "SWDCLK") (class "Default")
      (node (ref "DEBUG") (pin "4") (pinfunction "SWDCLK/TCK_4") (pintype "bidirectional"))
      (node (ref "DEBUG1") (pin "4") (pinfunction "SWDCLK/TCK_4") (pintype "bidirectional"))
      (node (ref "IC12") (pin "25") (pinfunction "SWDCLK_25") (pintype "bidirectional"))
      (node (ref "IC2") (pin "17") (pinfunction "PA14_17") (pintype "bidirectional"))
      (node (ref "R49") (pin "2") (pinfunction "2_2") (pintype "passive"))
    )
    (net (code "62") (name "SWDIO") (class "Default")
      (node (ref "DEBUG") (pin "2") (pinfunction "SWDIO/TMS_2") (pintype "bidirectional"))
      (node (ref "DEBUG1") (pin "2") (pinfunction "SWDIO/TMS_2") (pintype "bidirectional"))
      (node (ref "IC12") (pin "26") (pinfunction "SWDIO_26") (pintype "bidirectional"))
      (node (ref "IC2") (pin "16") (pinfunction "PA13_16") (pintype "bidirectional"))
    )
    (net (code "63") (name "USART2_RX") (class "Default")
      (node (ref "IC2") (pin "19") (pinfunction "PB7_19") (pintype "bidirectional"))
      (node (ref "UART") (pin "1") (pinfunction "1_1") (pintype "passive"))
    )
    (net (code "64") (name "USART2_TX") (class "Default")
      (node (ref "IC2") (pin "18") (pinfunction "PB6_18") (pintype "bidirectional"))
      (node (ref "UART") (pin "2") (pinfunction "2_2") (pintype "passive"))
    )
    (net (code "65") (name "V-ICHG") (class "Default")
      (node (ref "D1") (pin "A") (pinfunction "A_A") (pintype "passive"))
      (node (ref "IC12") (pin "6") (pinfunction "P0.04/AIN2_6") (pintype "bidirectional"))
      (node (ref "IC2") (pin "9") (pinfunction "PA6_9") (pintype "bidirectional"))
      (node (ref "IC4") (pin "1") (pinfunction "OUT_1") (pintype "output"))
      (node (ref "R5") (pin "2") (pinfunction "2_2") (pintype "passive"))
    )
    (net (code "66") (name "V-VCHG") (class "Default")
      (node (ref "C7") (pin "1") (pinfunction "P$1_1") (pintype "passive"))
      (node (ref "D2") (pin "A") (pinfunction "A_A") (pintype "passive"))
      (node (ref "IC12") (pin "5") (pinfunction "P0.03/AIN1_5") (pintype "bidirectional"))
      (node (ref "IC2") (pin "10") (pinfunction "PA7_10") (pintype "bidirectional"))
      (node (ref "R11") (pin "1") (pinfunction "1_1") (pintype "passive"))
      (node (ref "R12") (pin "1") (pinfunction "1_1") (pintype "passive"))
    )
    (net (code "67") (name "VCHG") (class "Default")
      (node (ref "C12") (pin "1") (pinfunction "P$1_1") (pintype "passive"))
      (node (ref "C13") (pin "1") (pinfunction "P$1_1") (pintype "passive"))
      (node (ref "C4") (pin "+") (pinfunction "+_+") (pintype "passive"))
      (node (ref "DEBUG") (pin "1") (pinfunction "VCC_1") (pintype "bidirectional"))
      (node (ref "IC2") (pin "13") (pinfunction "VDD_13") (pintype "bidirectional"))
      (node (ref "IC2") (pin "4") (pinfunction "VDDA_4") (pintype "bidirectional"))
      (node (ref "JP2") (pin "3") (pinfunction "3_3") (pintype "passive"))
      (node (ref "JP4") (pin "1") (pinfunction "1_1") (pintype "passive"))
      (node (ref "LS2") (pin "3") (pinfunction "VIN_3") (pintype "input"))
    )
    (net (code "68") (name "VDD_BLE") (class "Default")
      (node (ref "C66") (pin "1") (pinfunction "1_1") (pintype "passive"))
      (node (ref "C67") (pin "1") (pinfunction "1_1") (pintype "passive"))
      (node (ref "C68") (pin "1") (pinfunction "1_1") (pintype "passive"))
      (node (ref "DEBUG1") (pin "1") (pinfunction "VCC_1") (pintype "bidirectional"))
      (node (ref "IC12") (pin "13") (pinfunction "VDD_13") (pintype "bidirectional"))
      (node (ref "IC12") (pin "36") (pinfunction "VDD_36") (pintype "bidirectional"))
      (node (ref "IC12") (pin "48") (pinfunction "VDD_48") (pintype "bidirectional"))
      (node (ref "JP4") (pin "2") (pinfunction "2_2") (pintype "passive"))
      (node (ref "R50") (pin "2") (pinfunction "2_2") (pintype "passive"))
      (node (ref "R60") (pin "1") (pinfunction "1_1") (pintype "passive"))
    )
    (net (code "69") (name "VIN") (class "Default")
      (node (ref "C1") (pin "1") (pinfunction "P$1_1") (pintype "passive"))
      (node (ref "IC1") (pin "1") (pinfunction "VIN_1") (pintype "power_in"))
      (node (ref "IC3") (pin "3") (pinfunction "VIN_3") (pintype "input"))
      (node (ref "Q2") (pin "1") (pinfunction "D_1") (pintype "passive"))
      (node (ref "Q2") (pin "2") (pinfunction "D_2") (pintype "passive"))
      (node (ref "Q2") (pin "5") (pinfunction "D_5") (pintype "passive"))
      (node (ref "Q2") (pin "6") (pinfunction "D_6") (pintype "passive"))
      (node (ref "R13") (pin "1") (pinfunction "1_1") (pintype "passive"))
    )
    (net (code "70") (name "VMEAS") (class "Default")
      (node (ref "JP2") (pin "2") (pinfunction "2_2") (pintype "passive"))
      (node (ref "LS1") (pin "1") (pinfunction "VOUT_1") (pintype "output"))
      (node (ref "LS2") (pin "1") (pinfunction "VOUT_1") (pintype "output"))
      (node (ref "R11") (pin "2") (pinfunction "2_2") (pintype "passive"))
    )
    (net (code "71") (name "unconnected-(DEBUG-KEY-Pad7)") (class "Default")
      (node (ref "DEBUG") (pin "7") (pinfunction "KEY_7") (pintype "bidirectional"))
    )
    (net (code "72") (name "unconnected-(DEBUG-NC{slash}TDI-Pad8)") (class "Default")
      (node (ref "DEBUG") (pin "8") (pinfunction "NC/TDI_8") (pintype "bidirectional"))
    )
    (net (code "73") (name "unconnected-(DEBUG-SWO{slash}TDO-Pad6)") (class "Default")
      (node (ref "DEBUG") (pin "6") (pinfunction "SWO/TDO_6") (pintype "bidirectional"))
    )
    (net (code "74") (name "unconnected-(DEBUG1-KEY-Pad7)") (class "Default")
      (node (ref "DEBUG1") (pin "7") (pinfunction "KEY_7") (pintype "bidirectional"))
    )
    (net (code "75") (name "unconnected-(DEBUG1-NC{slash}TDI-Pad8)") (class "Default")
      (node (ref "DEBUG1") (pin "8") (pinfunction "NC/TDI_8") (pintype "bidirectional"))
    )
    (net (code "76") (name "unconnected-(IC2-PC14-Pad1)") (class "Default")
      (node (ref "IC2") (pin "1") (pinfunction "PC14_1") (pintype "bidirectional"))
    )
    (net (code "77") (name "unconnected-(IC2-PC15-Pad2)") (class "Default")
      (node (ref "IC2") (pin "2") (pinfunction "PC15_2") (pintype "bidirectional"))
    )
    (net (code "78") (name "unconnected-(IC12-NC-Pad44)") (class "Default")
      (node (ref "IC12") (pin "44") (pinfunction "NC_44") (pintype "bidirectional"))
    )
    (net (code "79") (name "unconnected-(U1-DIN-Pad3)") (class "Default")
      (node (ref "U1") (pin "3") (pinfunction "DIN_3") (pintype "input"))
    )
    (net (code "80") (name "unconnected-(U1-H-Pad8)") (class "Default")
      (node (ref "U1") (pin "8") (pinfunction "H_8") (pintype "bidirectional"))
    )
    (net (code "81") (name "unconnected-(U1-L-Pad6)") (class "Default")
      (node (ref "U1") (pin "6") (pinfunction "L_6") (pintype "bidirectional"))
    )
    (net (code "82") (name "unconnected-(U1-SCLK-Pad2)") (class "Default")
      (node (ref "U1") (pin "2") (pinfunction "SCLK_2") (pintype "input"))
    )
    (net (code "83") (name "unconnected-(U1-W-Pad7)") (class "Default")
      (node (ref "U1") (pin "7") (pinfunction "W_7") (pintype "bidirectional"))
    )
    (net (code "84") (name "unconnected-(U1-~{CS}-Pad4)") (class "Default")
      (node (ref "U1") (pin "4") (pinfunction "~{CS}_4") (pintype "input"))
    )
    (net (code "85") (name "~{RESET}") (class "Default")
      (node (ref "CRST") (pin "1") (pinfunction "1_1") (pintype "passive"))
      (node (ref "DEBUG1") (pin "10") (pinfunction "~{RESET}_10") (pintype "bidirectional"))
      (node (ref "IC12") (pin "24") (pinfunction "P0.21/RESET_24") (pintype "bidirectional"))
      (node (ref "R60") (pin "2") (pinfunction "2_2") (pintype "passive"))
    )
  )
)
